# FPGA_PWR.net
KiCad netlist of a schematic drawn in Altium Designer
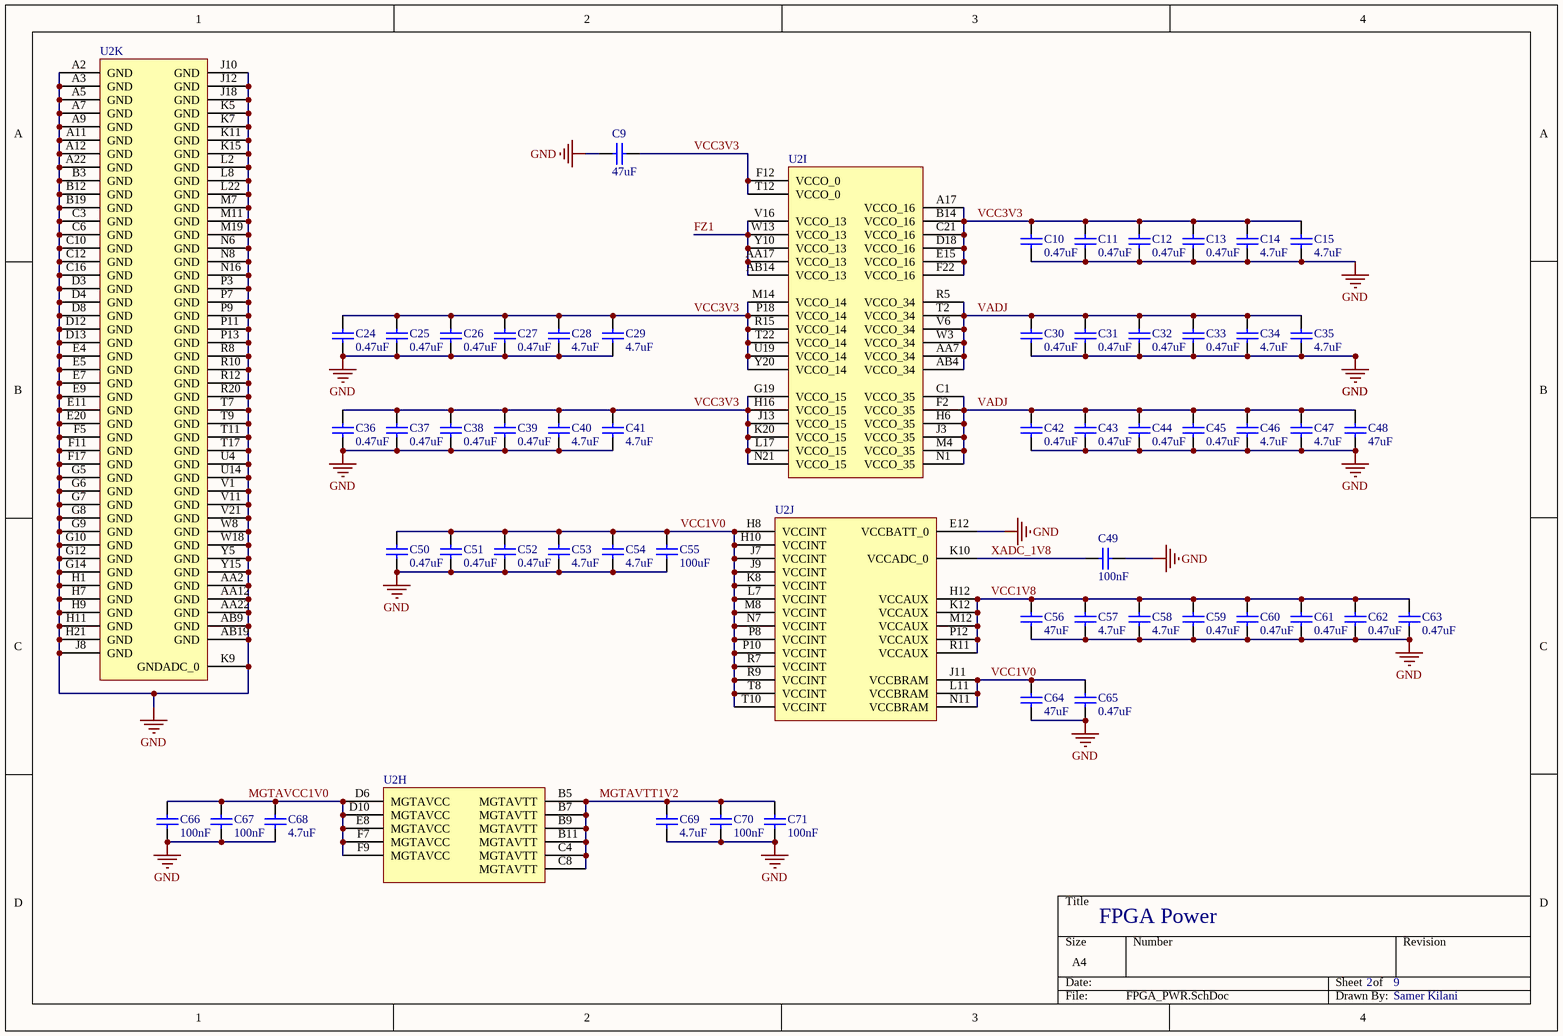
[diagram p0: FPGA_PWR.SchDoc]

(export (version "E")
  (design (tool "Eeschema 10.0.6"))
  (components
    (comp (ref "C9")
      (value "47uF")
      (footprint "C1210")
      (description "Capacitor")
      (fields (field (name "Comment") "Cap") (field (name "PUBLISHER") "Altium Limited"))
      (libsource (lib "atfclib") (part "Cap"))
    )
    (comp (ref "C10")
      (value "0.47uF")
      (footprint "C0402")
      (description "Capacitor")
      (fields (field (name "Comment") "Cap") (field (name "PUBLISHER") "Altium Limited"))
      (libsource (lib "atfclib") (part "Cap"))
    )
    (comp (ref "C11")
      (value "0.47uF")
      (footprint "C0402")
      (description "Capacitor")
      (fields (field (name "Comment") "Cap") (field (name "PUBLISHER") "Altium Limited"))
      (libsource (lib "atfclib") (part "Cap"))
    )
    (comp (ref "C12")
      (value "0.47uF")
      (footprint "C0402")
      (description "Capacitor")
      (fields (field (name "Comment") "Cap") (field (name "PUBLISHER") "Altium Limited"))
      (libsource (lib "atfclib") (part "Cap"))
    )
    (comp (ref "C13")
      (value "0.47uF")
      (footprint "C0402")
      (description "Capacitor")
      (fields (field (name "Comment") "Cap") (field (name "PUBLISHER") "Altium Limited"))
      (libsource (lib "atfclib") (part "Cap"))
    )
    (comp (ref "C14")
      (value "4.7uF")
      (footprint "C0805")
      (description "Capacitor")
      (fields (field (name "Comment") "Cap") (field (name "PUBLISHER") "Altium Limited"))
      (libsource (lib "atfclib") (part "Cap"))
    )
    (comp (ref "C15")
      (value "4.7uF")
      (footprint "C0805")
      (description "Capacitor")
      (fields (field (name "Comment") "Cap") (field (name "PUBLISHER") "Altium Limited"))
      (libsource (lib "atfclib") (part "Cap"))
    )
    (comp (ref "C24")
      (value "0.47uF")
      (footprint "C0402")
      (description "Capacitor")
      (fields (field (name "Comment") "Cap") (field (name "PUBLISHER") "Altium Limited"))
      (libsource (lib "atfclib") (part "Cap"))
    )
    (comp (ref "C25")
      (value "0.47uF")
      (footprint "C0402")
      (description "Capacitor")
      (fields (field (name "Comment") "Cap") (field (name "PUBLISHER") "Altium Limited"))
      (libsource (lib "atfclib") (part "Cap"))
    )
    (comp (ref "C26")
      (value "0.47uF")
      (footprint "C0402")
      (description "Capacitor")
      (fields (field (name "Comment") "Cap") (field (name "PUBLISHER") "Altium Limited"))
      (libsource (lib "atfclib") (part "Cap"))
    )
    (comp (ref "C27")
      (value "0.47uF")
      (footprint "C0402")
      (description "Capacitor")
      (fields (field (name "Comment") "Cap") (field (name "PUBLISHER") "Altium Limited"))
      (libsource (lib "atfclib") (part "Cap"))
    )
    (comp (ref "C28")
      (value "4.7uF")
      (footprint "C0805")
      (description "Capacitor")
      (fields (field (name "Comment") "Cap") (field (name "PUBLISHER") "Altium Limited"))
      (libsource (lib "atfclib") (part "Cap"))
    )
    (comp (ref "C29")
      (value "4.7uF")
      (footprint "C0805")
      (description "Capacitor")
      (fields (field (name "Comment") "Cap") (field (name "PUBLISHER") "Altium Limited"))
      (libsource (lib "atfclib") (part "Cap"))
    )
    (comp (ref "C30")
      (value "0.47uF")
      (footprint "C0402")
      (description "Capacitor")
      (fields (field (name "Comment") "Cap") (field (name "PUBLISHER") "Altium Limited"))
      (libsource (lib "atfclib") (part "Cap"))
    )
    (comp (ref "C31")
      (value "0.47uF")
      (footprint "C0402")
      (description "Capacitor")
      (fields (field (name "Comment") "Cap") (field (name "PUBLISHER") "Altium Limited"))
      (libsource (lib "atfclib") (part "Cap"))
    )
    (comp (ref "C32")
      (value "0.47uF")
      (footprint "C0402")
      (description "Capacitor")
      (fields (field (name "Comment") "Cap") (field (name "PUBLISHER") "Altium Limited"))
      (libsource (lib "atfclib") (part "Cap"))
    )
    (comp (ref "C33")
      (value "0.47uF")
      (footprint "C0402")
      (description "Capacitor")
      (fields (field (name "Comment") "Cap") (field (name "PUBLISHER") "Altium Limited"))
      (libsource (lib "atfclib") (part "Cap"))
    )
    (comp (ref "C34")
      (value "4.7uF")
      (footprint "C0805")
      (description "Capacitor")
      (fields (field (name "Comment") "Cap") (field (name "PUBLISHER") "Altium Limited"))
      (libsource (lib "atfclib") (part "Cap"))
    )
    (comp (ref "C35")
      (value "4.7uF")
      (footprint "C0805")
      (description "Capacitor")
      (fields (field (name "Comment") "Cap") (field (name "PUBLISHER") "Altium Limited"))
      (libsource (lib "atfclib") (part "Cap"))
    )
    (comp (ref "C36")
      (value "0.47uF")
      (footprint "C0402")
      (description "Capacitor")
      (fields (field (name "Comment") "Cap") (field (name "PUBLISHER") "Altium Limited"))
      (libsource (lib "atfclib") (part "Cap"))
    )
    (comp (ref "C37")
      (value "0.47uF")
      (footprint "C0402")
      (description "Capacitor")
      (fields (field (name "Comment") "Cap") (field (name "PUBLISHER") "Altium Limited"))
      (libsource (lib "atfclib") (part "Cap"))
    )
    (comp (ref "C38")
      (value "0.47uF")
      (footprint "C0402")
      (description "Capacitor")
      (fields (field (name "Comment") "Cap") (field (name "PUBLISHER") "Altium Limited"))
      (libsource (lib "atfclib") (part "Cap"))
    )
    (comp (ref "C39")
      (value "0.47uF")
      (footprint "C0402")
      (description "Capacitor")
      (fields (field (name "Comment") "Cap") (field (name "PUBLISHER") "Altium Limited"))
      (libsource (lib "atfclib") (part "Cap"))
    )
    (comp (ref "C40")
      (value "4.7uF")
      (footprint "C0805")
      (description "Capacitor")
      (fields (field (name "Comment") "Cap") (field (name "PUBLISHER") "Altium Limited"))
      (libsource (lib "atfclib") (part "Cap"))
    )
    (comp (ref "C41")
      (value "4.7uF")
      (footprint "C0805")
      (description "Capacitor")
      (fields (field (name "Comment") "Cap") (field (name "PUBLISHER") "Altium Limited"))
      (libsource (lib "atfclib") (part "Cap"))
    )
    (comp (ref "C42")
      (value "0.47uF")
      (footprint "C0402")
      (description "Capacitor")
      (fields (field (name "Comment") "Cap") (field (name "PUBLISHER") "Altium Limited"))
      (libsource (lib "atfclib") (part "Cap"))
    )
    (comp (ref "C43")
      (value "0.47uF")
      (footprint "C0402")
      (description "Capacitor")
      (fields (field (name "Comment") "Cap") (field (name "PUBLISHER") "Altium Limited"))
      (libsource (lib "atfclib") (part "Cap"))
    )
    (comp (ref "C44")
      (value "0.47uF")
      (footprint "C0402")
      (description "Capacitor")
      (fields (field (name "Comment") "Cap") (field (name "PUBLISHER") "Altium Limited"))
      (libsource (lib "atfclib") (part "Cap"))
    )
    (comp (ref "C45")
      (value "0.47uF")
      (footprint "C0402")
      (description "Capacitor")
      (fields (field (name "Comment") "Cap") (field (name "PUBLISHER") "Altium Limited"))
      (libsource (lib "atfclib") (part "Cap"))
    )
    (comp (ref "C46")
      (value "4.7uF")
      (footprint "C0805")
      (description "Capacitor")
      (fields (field (name "Comment") "Cap") (field (name "PUBLISHER") "Altium Limited"))
      (libsource (lib "atfclib") (part "Cap"))
    )
    (comp (ref "C47")
      (value "4.7uF")
      (footprint "C0805")
      (description "Capacitor")
      (fields (field (name "Comment") "Cap") (field (name "PUBLISHER") "Altium Limited"))
      (libsource (lib "atfclib") (part "Cap"))
    )
    (comp (ref "C48")
      (value "47uF")
      (footprint "C1210")
      (description "Capacitor")
      (fields (field (name "Comment") "Cap") (field (name "PUBLISHER") "Altium Limited"))
      (libsource (lib "atfclib") (part "Cap"))
    )
    (comp (ref "C49")
      (value "100nF")
      (footprint "C0402")
      (description "Capacitor")
      (fields (field (name "Comment") "Cap") (field (name "PUBLISHER") "Altium Limited"))
      (libsource (lib "atfclib") (part "Cap"))
    )
    (comp (ref "C50")
      (value "0.47uF")
      (footprint "C0402")
      (description "Capacitor")
      (fields (field (name "Comment") "Cap") (field (name "PUBLISHER") "Altium Limited"))
      (libsource (lib "atfclib") (part "Cap"))
    )
    (comp (ref "C51")
      (value "0.47uF")
      (footprint "C0402")
      (description "Capacitor")
      (fields (field (name "Comment") "Cap") (field (name "PUBLISHER") "Altium Limited"))
      (libsource (lib "atfclib") (part "Cap"))
    )
    (comp (ref "C52")
      (value "0.47uF")
      (footprint "C0402")
      (description "Capacitor")
      (fields (field (name "Comment") "Cap") (field (name "PUBLISHER") "Altium Limited"))
      (libsource (lib "atfclib") (part "Cap"))
    )
    (comp (ref "C53")
      (value "4.7uF")
      (footprint "C0805")
      (description "Capacitor")
      (fields (field (name "Comment") "Cap") (field (name "PUBLISHER") "Altium Limited"))
      (libsource (lib "atfclib") (part "Cap"))
    )
    (comp (ref "C54")
      (value "4.7uF")
      (footprint "C0805")
      (description "Capacitor")
      (fields (field (name "Comment") "Cap") (field (name "PUBLISHER") "Altium Limited"))
      (libsource (lib "atfclib") (part "Cap"))
    )
    (comp (ref "C55")
      (value "100uF")
      (footprint "C1210")
      (description "Capacitor")
      (fields (field (name "Comment") "Cap") (field (name "PUBLISHER") "Altium Limited"))
      (libsource (lib "atfclib") (part "Cap"))
    )
    (comp (ref "C56")
      (value "47uF")
      (footprint "C1210")
      (description "Capacitor")
      (fields (field (name "Comment") "Cap") (field (name "PUBLISHER") "Altium Limited"))
      (libsource (lib "atfclib") (part "Cap"))
    )
    (comp (ref "C57")
      (value "4.7uF")
      (footprint "C0805")
      (description "Capacitor")
      (fields (field (name "Comment") "Cap") (field (name "PUBLISHER") "Altium Limited"))
      (libsource (lib "atfclib") (part "Cap"))
    )
    (comp (ref "C58")
      (value "4.7uF")
      (footprint "C0805")
      (description "Capacitor")
      (fields (field (name "Comment") "Cap") (field (name "PUBLISHER") "Altium Limited"))
      (libsource (lib "atfclib") (part "Cap"))
    )
    (comp (ref "C59")
      (value "0.47uF")
      (footprint "C0402")
      (description "Capacitor")
      (fields (field (name "Comment") "Cap") (field (name "PUBLISHER") "Altium Limited"))
      (libsource (lib "atfclib") (part "Cap"))
    )
    (comp (ref "C60")
      (value "0.47uF")
      (footprint "C0402")
      (description "Capacitor")
      (fields (field (name "Comment") "Cap") (field (name "PUBLISHER") "Altium Limited"))
      (libsource (lib "atfclib") (part "Cap"))
    )
    (comp (ref "C61")
      (value "0.47uF")
      (footprint "C0402")
      (description "Capacitor")
      (fields (field (name "Comment") "Cap") (field (name "PUBLISHER") "Altium Limited"))
      (libsource (lib "atfclib") (part "Cap"))
    )
    (comp (ref "C62")
      (value "0.47uF")
      (footprint "C0402")
      (description "Capacitor")
      (fields (field (name "Comment") "Cap") (field (name "PUBLISHER") "Altium Limited"))
      (libsource (lib "atfclib") (part "Cap"))
    )
    (comp (ref "C63")
      (value "0.47uF")
      (footprint "C0402")
      (description "Capacitor")
      (fields (field (name "Comment") "Cap") (field (name "PUBLISHER") "Altium Limited"))
      (libsource (lib "atfclib") (part "Cap"))
    )
    (comp (ref "C64")
      (value "47uF")
      (footprint "C1210")
      (description "Capacitor")
      (fields (field (name "Comment") "Cap") (field (name "PUBLISHER") "Altium Limited"))
      (libsource (lib "atfclib") (part "Cap"))
    )
    (comp (ref "C65")
      (value "0.47uF")
      (footprint "C0402")
      (description "Capacitor")
      (fields (field (name "Comment") "Cap") (field (name "PUBLISHER") "Altium Limited"))
      (libsource (lib "atfclib") (part "Cap"))
    )
    (comp (ref "C66")
      (value "100nF")
      (footprint "C0402")
      (description "Capacitor")
      (fields (field (name "Comment") "Cap") (field (name "PUBLISHER") "Altium Limited"))
      (libsource (lib "atfclib") (part "Cap"))
    )
    (comp (ref "C67")
      (value "100nF")
      (footprint "C0402")
      (description "Capacitor")
      (fields (field (name "Comment") "Cap") (field (name "PUBLISHER") "Altium Limited"))
      (libsource (lib "atfclib") (part "Cap"))
    )
    (comp (ref "C68")
      (value "4.7uF")
      (footprint "C0805")
      (description "Capacitor")
      (fields (field (name "Comment") "Cap") (field (name "PUBLISHER") "Altium Limited"))
      (libsource (lib "atfclib") (part "Cap"))
    )
    (comp (ref "C69")
      (value "4.7uF")
      (footprint "C0805")
      (description "Capacitor")
      (fields (field (name "Comment") "Cap") (field (name "PUBLISHER") "Altium Limited"))
      (libsource (lib "atfclib") (part "Cap"))
    )
    (comp (ref "C70")
      (value "100nF")
      (footprint "C0402")
      (description "Capacitor")
      (fields (field (name "Comment") "Cap") (field (name "PUBLISHER") "Altium Limited"))
      (libsource (lib "atfclib") (part "Cap"))
    )
    (comp (ref "C71")
      (value "100nF")
      (footprint "C0402")
      (description "Capacitor")
      (fields (field (name "Comment") "Cap") (field (name "PUBLISHER") "Altium Limited"))
      (libsource (lib "atfclib") (part "Cap"))
    )
    (comp (ref "U2")
      (value "~")
      (footprint "FGG484")
      (description "Artix-7 FPGA, 250 User I/Os, 4 GTP, 484-Ball BGA, Speed Grade 1, Commercial Grade, Pb-Free")
      (fields (field (name "MANUFACTURER") "Xilinx") (field (name "PARTNUMBER") "XC7A35T-1FGG484C"))
      (libsource (lib "atfclib") (part "XC7A35T-1FGG484C"))
    )
  )
  (nets
    (net (code "1") (name "/FZ1") (class "Default")
      (node (ref "U2") (pin "AA17") (pinfunction "VCCO_13_AA17") (pintype "power_in"))
      (node (ref "U2") (pin "AB14") (pinfunction "VCCO_13_AB14") (pintype "power_in"))
      (node (ref "U2") (pin "V16") (pinfunction "VCCO_13_V16") (pintype "power_in"))
      (node (ref "U2") (pin "W13") (pinfunction "VCCO_13_W13") (pintype "power_in"))
      (node (ref "U2") (pin "Y10") (pinfunction "VCCO_13_Y10") (pintype "power_in"))
    )
    (net (code "2") (name "/MGTAVCC1V0") (class "Default")
      (node (ref "C66") (pin "1") (pinfunction "1_1") (pintype "passive"))
      (node (ref "C67") (pin "1") (pinfunction "1_1") (pintype "passive"))
      (node (ref "C68") (pin "1") (pinfunction "1_1") (pintype "passive"))
      (node (ref "U2") (pin "D10") (pinfunction "MGTAVCC_D10") (pintype "power_in"))
      (node (ref "U2") (pin "D6") (pinfunction "MGTAVCC_D6") (pintype "power_in"))
      (node (ref "U2") (pin "E8") (pinfunction "MGTAVCC_E8") (pintype "power_in"))
      (node (ref "U2") (pin "F7") (pinfunction "MGTAVCC_F7") (pintype "power_in"))
      (node (ref "U2") (pin "F9") (pinfunction "MGTAVCC_F9") (pintype "power_in"))
    )
    (net (code "3") (name "/MGTAVTT1V2") (class "Default")
      (node (ref "C69") (pin "2") (pinfunction "2_2") (pintype "passive"))
      (node (ref "C70") (pin "2") (pinfunction "2_2") (pintype "passive"))
      (node (ref "C71") (pin "2") (pinfunction "2_2") (pintype "passive"))
      (node (ref "U2") (pin "B11") (pinfunction "MGTAVTT_B11") (pintype "power_in"))
      (node (ref "U2") (pin "B5") (pinfunction "MGTAVTT_B5") (pintype "power_in"))
      (node (ref "U2") (pin "B7") (pinfunction "MGTAVTT_B7") (pintype "power_in"))
      (node (ref "U2") (pin "B9") (pinfunction "MGTAVTT_B9") (pintype "power_in"))
      (node (ref "U2") (pin "C4") (pinfunction "MGTAVTT_C4") (pintype "power_in"))
      (node (ref "U2") (pin "C8") (pinfunction "MGTAVTT_C8") (pintype "power_in"))
    )
    (net (code "4") (name "/VADJ") (class "Default")
      (node (ref "C30") (pin "1") (pinfunction "1_1") (pintype "passive"))
      (node (ref "C31") (pin "1") (pinfunction "1_1") (pintype "passive"))
      (node (ref "C32") (pin "1") (pinfunction "1_1") (pintype "passive"))
      (node (ref "C33") (pin "1") (pinfunction "1_1") (pintype "passive"))
      (node (ref "C34") (pin "1") (pinfunction "1_1") (pintype "passive"))
      (node (ref "C35") (pin "1") (pinfunction "1_1") (pintype "passive"))
      (node (ref "C42") (pin "1") (pinfunction "1_1") (pintype "passive"))
      (node (ref "C43") (pin "1") (pinfunction "1_1") (pintype "passive"))
      (node (ref "C44") (pin "1") (pinfunction "1_1") (pintype "passive"))
      (node (ref "C45") (pin "1") (pinfunction "1_1") (pintype "passive"))
      (node (ref "C46") (pin "1") (pinfunction "1_1") (pintype "passive"))
      (node (ref "C47") (pin "1") (pinfunction "1_1") (pintype "passive"))
      (node (ref "C48") (pin "1") (pinfunction "1_1") (pintype "passive"))
      (node (ref "U2") (pin "AA7") (pinfunction "VCCO_34_AA7") (pintype "power_in"))
      (node (ref "U2") (pin "AB4") (pinfunction "VCCO_34_AB4") (pintype "power_in"))
      (node (ref "U2") (pin "C1") (pinfunction "VCCO_35_C1") (pintype "power_in"))
      (node (ref "U2") (pin "F2") (pinfunction "VCCO_35_F2") (pintype "power_in"))
      (node (ref "U2") (pin "H6") (pinfunction "VCCO_35_H6") (pintype "power_in"))
      (node (ref "U2") (pin "J3") (pinfunction "VCCO_35_J3") (pintype "power_in"))
      (node (ref "U2") (pin "M4") (pinfunction "VCCO_35_M4") (pintype "power_in"))
      (node (ref "U2") (pin "N1") (pinfunction "VCCO_35_N1") (pintype "power_in"))
      (node (ref "U2") (pin "R5") (pinfunction "VCCO_34_R5") (pintype "power_in"))
      (node (ref "U2") (pin "T2") (pinfunction "VCCO_34_T2") (pintype "power_in"))
      (node (ref "U2") (pin "V6") (pinfunction "VCCO_34_V6") (pintype "power_in"))
      (node (ref "U2") (pin "W3") (pinfunction "VCCO_34_W3") (pintype "power_in"))
    )
    (net (code "5") (name "/VCC1V0") (class "Default")
      (node (ref "C50") (pin "1") (pinfunction "1_1") (pintype "passive"))
      (node (ref "C51") (pin "1") (pinfunction "1_1") (pintype "passive"))
      (node (ref "C52") (pin "1") (pinfunction "1_1") (pintype "passive"))
      (node (ref "C53") (pin "1") (pinfunction "1_1") (pintype "passive"))
      (node (ref "C54") (pin "1") (pinfunction "1_1") (pintype "passive"))
      (node (ref "C55") (pin "1") (pinfunction "1_1") (pintype "passive"))
      (node (ref "C64") (pin "1") (pinfunction "1_1") (pintype "passive"))
      (node (ref "C65") (pin "1") (pinfunction "1_1") (pintype "passive"))
      (node (ref "U2") (pin "H10") (pinfunction "VCCINT_H10") (pintype "power_in"))
      (node (ref "U2") (pin "H8") (pinfunction "VCCINT_H8") (pintype "power_in"))
      (node (ref "U2") (pin "J11") (pinfunction "VCCBRAM_J11") (pintype "power_in"))
      (node (ref "U2") (pin "J7") (pinfunction "VCCINT_J7") (pintype "power_in"))
      (node (ref "U2") (pin "J9") (pinfunction "VCCINT_J9") (pintype "power_in"))
      (node (ref "U2") (pin "K8") (pinfunction "VCCINT_K8") (pintype "power_in"))
      (node (ref "U2") (pin "L11") (pinfunction "VCCBRAM_L11") (pintype "power_in"))
      (node (ref "U2") (pin "L7") (pinfunction "VCCINT_L7") (pintype "power_in"))
      (node (ref "U2") (pin "M8") (pinfunction "VCCINT_M8") (pintype "power_in"))
      (node (ref "U2") (pin "N11") (pinfunction "VCCBRAM_N11") (pintype "power_in"))
      (node (ref "U2") (pin "N7") (pinfunction "VCCINT_N7") (pintype "power_in"))
      (node (ref "U2") (pin "P10") (pinfunction "VCCINT_P10") (pintype "power_in"))
      (node (ref "U2") (pin "P8") (pinfunction "VCCINT_P8") (pintype "power_in"))
      (node (ref "U2") (pin "R7") (pinfunction "VCCINT_R7") (pintype "power_in"))
      (node (ref "U2") (pin "R9") (pinfunction "VCCINT_R9") (pintype "power_in"))
      (node (ref "U2") (pin "T10") (pinfunction "VCCINT_T10") (pintype "power_in"))
      (node (ref "U2") (pin "T8") (pinfunction "VCCINT_T8") (pintype "power_in"))
    )
    (net (code "6") (name "/VCC1V8") (class "Default")
      (node (ref "C56") (pin "1") (pinfunction "1_1") (pintype "passive"))
      (node (ref "C57") (pin "1") (pinfunction "1_1") (pintype "passive"))
      (node (ref "C58") (pin "1") (pinfunction "1_1") (pintype "passive"))
      (node (ref "C59") (pin "1") (pinfunction "1_1") (pintype "passive"))
      (node (ref "C60") (pin "1") (pinfunction "1_1") (pintype "passive"))
      (node (ref "C61") (pin "1") (pinfunction "1_1") (pintype "passive"))
      (node (ref "C62") (pin "1") (pinfunction "1_1") (pintype "passive"))
      (node (ref "C63") (pin "1") (pinfunction "1_1") (pintype "passive"))
      (node (ref "U2") (pin "H12") (pinfunction "VCCAUX_H12") (pintype "power_in"))
      (node (ref "U2") (pin "K12") (pinfunction "VCCAUX_K12") (pintype "power_in"))
      (node (ref "U2") (pin "M12") (pinfunction "VCCAUX_M12") (pintype "power_in"))
      (node (ref "U2") (pin "P12") (pinfunction "VCCAUX_P12") (pintype "power_in"))
      (node (ref "U2") (pin "R11") (pinfunction "VCCAUX_R11") (pintype "power_in"))
    )
    (net (code "7") (name "/VCC3V3") (class "Default")
      (node (ref "C10") (pin "1") (pinfunction "1_1") (pintype "passive"))
      (node (ref "C11") (pin "1") (pinfunction "1_1") (pintype "passive"))
      (node (ref "C12") (pin "1") (pinfunction "1_1") (pintype "passive"))
      (node (ref "C13") (pin "1") (pinfunction "1_1") (pintype "passive"))
      (node (ref "C14") (pin "1") (pinfunction "1_1") (pintype "passive"))
      (node (ref "C15") (pin "1") (pinfunction "1_1") (pintype "passive"))
      (node (ref "C24") (pin "1") (pinfunction "1_1") (pintype "passive"))
      (node (ref "C25") (pin "1") (pinfunction "1_1") (pintype "passive"))
      (node (ref "C26") (pin "1") (pinfunction "1_1") (pintype "passive"))
      (node (ref "C27") (pin "1") (pinfunction "1_1") (pintype "passive"))
      (node (ref "C28") (pin "1") (pinfunction "1_1") (pintype "passive"))
      (node (ref "C29") (pin "1") (pinfunction "1_1") (pintype "passive"))
      (node (ref "C36") (pin "1") (pinfunction "1_1") (pintype "passive"))
      (node (ref "C37") (pin "1") (pinfunction "1_1") (pintype "passive"))
      (node (ref "C38") (pin "1") (pinfunction "1_1") (pintype "passive"))
      (node (ref "C39") (pin "1") (pinfunction "1_1") (pintype "passive"))
      (node (ref "C40") (pin "1") (pinfunction "1_1") (pintype "passive"))
      (node (ref "C41") (pin "1") (pinfunction "1_1") (pintype "passive"))
      (node (ref "C9") (pin "1") (pinfunction "1_1") (pintype "passive"))
      (node (ref "U2") (pin "A17") (pinfunction "VCCO_16_A17") (pintype "power_in"))
      (node (ref "U2") (pin "B14") (pinfunction "VCCO_16_B14") (pintype "power_in"))
      (node (ref "U2") (pin "C21") (pinfunction "VCCO_16_C21") (pintype "power_in"))
      (node (ref "U2") (pin "D18") (pinfunction "VCCO_16_D18") (pintype "power_in"))
      (node (ref "U2") (pin "E15") (pinfunction "VCCO_16_E15") (pintype "power_in"))
      (node (ref "U2") (pin "F12") (pinfunction "VCCO_0_F12") (pintype "power_in"))
      (node (ref "U2") (pin "F22") (pinfunction "VCCO_16_F22") (pintype "power_in"))
      (node (ref "U2") (pin "G19") (pinfunction "VCCO_15_G19") (pintype "power_in"))
      (node (ref "U2") (pin "H16") (pinfunction "VCCO_15_H16") (pintype "power_in"))
      (node (ref "U2") (pin "J13") (pinfunction "VCCO_15_J13") (pintype "power_in"))
      (node (ref "U2") (pin "K20") (pinfunction "VCCO_15_K20") (pintype "power_in"))
      (node (ref "U2") (pin "L17") (pinfunction "VCCO_15_L17") (pintype "power_in"))
      (node (ref "U2") (pin "M14") (pinfunction "VCCO_14_M14") (pintype "power_in"))
      (node (ref "U2") (pin "N21") (pinfunction "VCCO_15_N21") (pintype "power_in"))
      (node (ref "U2") (pin "P18") (pinfunction "VCCO_14_P18") (pintype "power_in"))
      (node (ref "U2") (pin "R15") (pinfunction "VCCO_14_R15") (pintype "power_in"))
      (node (ref "U2") (pin "T12") (pinfunction "VCCO_0_T12") (pintype "power_in"))
      (node (ref "U2") (pin "T22") (pinfunction "VCCO_14_T22") (pintype "power_in"))
      (node (ref "U2") (pin "U19") (pinfunction "VCCO_14_U19") (pintype "power_in"))
      (node (ref "U2") (pin "Y20") (pinfunction "VCCO_14_Y20") (pintype "power_in"))
    )
    (net (code "8") (name "/XADC_1V8") (class "Default")
      (node (ref "C49") (pin "2") (pinfunction "2_2") (pintype "passive"))
      (node (ref "U2") (pin "K10") (pinfunction "VCCADC_0_K10") (pintype "power_in"))
    )
    (net (code "9") (name "GND") (class "Default")
      (node (ref "C10") (pin "2") (pinfunction "2_2") (pintype "passive"))
      (node (ref "C11") (pin "2") (pinfunction "2_2") (pintype "passive"))
      (node (ref "C12") (pin "2") (pinfunction "2_2") (pintype "passive"))
      (node (ref "C13") (pin "2") (pinfunction "2_2") (pintype "passive"))
      (node (ref "C14") (pin "2") (pinfunction "2_2") (pintype "passive"))
      (node (ref "C15") (pin "2") (pinfunction "2_2") (pintype "passive"))
      (node (ref "C24") (pin "2") (pinfunction "2_2") (pintype "passive"))
      (node (ref "C25") (pin "2") (pinfunction "2_2") (pintype "passive"))
      (node (ref "C26") (pin "2") (pinfunction "2_2") (pintype "passive"))
      (node (ref "C27") (pin "2") (pinfunction "2_2") (pintype "passive"))
      (node (ref "C28") (pin "2") (pinfunction "2_2") (pintype "passive"))
      (node (ref "C29") (pin "2") (pinfunction "2_2") (pintype "passive"))
      (node (ref "C30") (pin "2") (pinfunction "2_2") (pintype "passive"))
      (node (ref "C31") (pin "2") (pinfunction "2_2") (pintype "passive"))
      (node (ref "C32") (pin "2") (pinfunction "2_2") (pintype "passive"))
      (node (ref "C33") (pin "2") (pinfunction "2_2") (pintype "passive"))
      (node (ref "C34") (pin "2") (pinfunction "2_2") (pintype "passive"))
      (node (ref "C35") (pin "2") (pinfunction "2_2") (pintype "passive"))
      (node (ref "C36") (pin "2") (pinfunction "2_2") (pintype "passive"))
      (node (ref "C37") (pin "2") (pinfunction "2_2") (pintype "passive"))
      (node (ref "C38") (pin "2") (pinfunction "2_2") (pintype "passive"))
      (node (ref "C39") (pin "2") (pinfunction "2_2") (pintype "passive"))
      (node (ref "C40") (pin "2") (pinfunction "2_2") (pintype "passive"))
      (node (ref "C41") (pin "2") (pinfunction "2_2") (pintype "passive"))
      (node (ref "C42") (pin "2") (pinfunction "2_2") (pintype "passive"))
      (node (ref "C43") (pin "2") (pinfunction "2_2") (pintype "passive"))
      (node (ref "C44") (pin "2") (pinfunction "2_2") (pintype "passive"))
      (node (ref "C45") (pin "2") (pinfunction "2_2") (pintype "passive"))
      (node (ref "C46") (pin "2") (pinfunction "2_2") (pintype "passive"))
      (node (ref "C47") (pin "2") (pinfunction "2_2") (pintype "passive"))
      (node (ref "C48") (pin "2") (pinfunction "2_2") (pintype "passive"))
      (node (ref "C49") (pin "1") (pinfunction "1_1") (pintype "passive"))
      (node (ref "C50") (pin "2") (pinfunction "2_2") (pintype "passive"))
      (node (ref "C51") (pin "2") (pinfunction "2_2") (pintype "passive"))
      (node (ref "C52") (pin "2") (pinfunction "2_2") (pintype "passive"))
      (node (ref "C53") (pin "2") (pinfunction "2_2") (pintype "passive"))
      (node (ref "C54") (pin "2") (pinfunction "2_2") (pintype "passive"))
      (node (ref "C55") (pin "2") (pinfunction "2_2") (pintype "passive"))
      (node (ref "C56") (pin "2") (pinfunction "2_2") (pintype "passive"))
      (node (ref "C57") (pin "2") (pinfunction "2_2") (pintype "passive"))
      (node (ref "C58") (pin "2") (pinfunction "2_2") (pintype "passive"))
      (node (ref "C59") (pin "2") (pinfunction "2_2") (pintype "passive"))
      (node (ref "C60") (pin "2") (pinfunction "2_2") (pintype "passive"))
      (node (ref "C61") (pin "2") (pinfunction "2_2") (pintype "passive"))
      (node (ref "C62") (pin "2") (pinfunction "2_2") (pintype "passive"))
      (node (ref "C63") (pin "2") (pinfunction "2_2") (pintype "passive"))
      (node (ref "C64") (pin "2") (pinfunction "2_2") (pintype "passive"))
      (node (ref "C65") (pin "2") (pinfunction "2_2") (pintype "passive"))
      (node (ref "C66") (pin "2") (pinfunction "2_2") (pintype "passive"))
      (node (ref "C67") (pin "2") (pinfunction "2_2") (pintype "passive"))
      (node (ref "C68") (pin "2") (pinfunction "2_2") (pintype "passive"))
      (node (ref "C69") (pin "1") (pinfunction "1_1") (pintype "passive"))
      (node (ref "C70") (pin "1") (pinfunction "1_1") (pintype "passive"))
      (node (ref "C71") (pin "1") (pinfunction "1_1") (pintype "passive"))
      (node (ref "C9") (pin "2") (pinfunction "2_2") (pintype "passive"))
      (node (ref "U2") (pin "A11") (pinfunction "GND_A11") (pintype "power_in"))
      (node (ref "U2") (pin "A12") (pinfunction "GND_A12") (pintype "power_in"))
      (node (ref "U2") (pin "A2") (pinfunction "GND_A2") (pintype "power_in"))
      (node (ref "U2") (pin "A22") (pinfunction "GND_A22") (pintype "power_in"))
      (node (ref "U2") (pin "A3") (pinfunction "GND_A3") (pintype "power_in"))
      (node (ref "U2") (pin "A5") (pinfunction "GND_A5") (pintype "power_in"))
      (node (ref "U2") (pin "A7") (pinfunction "GND_A7") (pintype "power_in"))
      (node (ref "U2") (pin "A9") (pinfunction "GND_A9") (pintype "power_in"))
      (node (ref "U2") (pin "AA12") (pinfunction "GND_AA12") (pintype "power_in"))
      (node (ref "U2") (pin "AA2") (pinfunction "GND_AA2") (pintype "power_in"))
      (node (ref "U2") (pin "AA22") (pinfunction "GND_AA22") (pintype "power_in"))
      (node (ref "U2") (pin "AB19") (pinfunction "GND_AB19") (pintype "power_in"))
      (node (ref "U2") (pin "AB9") (pinfunction "GND_AB9") (pintype "power_in"))
      (node (ref "U2") (pin "B12") (pinfunction "GND_B12") (pintype "power_in"))
      (node (ref "U2") (pin "B19") (pinfunction "GND_B19") (pintype "power_in"))
      (node (ref "U2") (pin "B3") (pinfunction "GND_B3") (pintype "power_in"))
      (node (ref "U2") (pin "C10") (pinfunction "GND_C10") (pintype "power_in"))
      (node (ref "U2") (pin "C12") (pinfunction "GND_C12") (pintype "power_in"))
      (node (ref "U2") (pin "C16") (pinfunction "GND_C16") (pintype "power_in"))
      (node (ref "U2") (pin "C3") (pinfunction "GND_C3") (pintype "power_in"))
      (node (ref "U2") (pin "C6") (pinfunction "GND_C6") (pintype "power_in"))
      (node (ref "U2") (pin "D12") (pinfunction "GND_D12") (pintype "power_in"))
      (node (ref "U2") (pin "D13") (pinfunction "GND_D13") (pintype "power_in"))
      (node (ref "U2") (pin "D3") (pinfunction "GND_D3") (pintype "power_in"))
      (node (ref "U2") (pin "D4") (pinfunction "GND_D4") (pintype "power_in"))
      (node (ref "U2") (pin "D8") (pinfunction "GND_D8") (pintype "power_in"))
      (node (ref "U2") (pin "E11") (pinfunction "GND_E11") (pintype "power_in"))
      (node (ref "U2") (pin "E12") (pinfunction "VCCBATT_0_E12") (pintype "power_in"))
      (node (ref "U2") (pin "E20") (pinfunction "GND_E20") (pintype "power_in"))
      (node (ref "U2") (pin "E4") (pinfunction "GND_E4") (pintype "power_in"))
      (node (ref "U2") (pin "E5") (pinfunction "GND_E5") (pintype "power_in"))
      (node (ref "U2") (pin "E7") (pinfunction "GND_E7") (pintype "power_in"))
      (node (ref "U2") (pin "E9") (pinfunction "GND_E9") (pintype "power_in"))
      (node (ref "U2") (pin "F11") (pinfunction "GND_F11") (pintype "power_in"))
      (node (ref "U2") (pin "F17") (pinfunction "GND_F17") (pintype "power_in"))
      (node (ref "U2") (pin "F5") (pinfunction "GND_F5") (pintype "power_in"))
      (node (ref "U2") (pin "G10") (pinfunction "GND_G10") (pintype "power_in"))
      (node (ref "U2") (pin "G12") (pinfunction "GND_G12") (pintype "power_in"))
      (node (ref "U2") (pin "G14") (pinfunction "GND_G14") (pintype "power_in"))
      (node (ref "U2") (pin "G5") (pinfunction "GND_G5") (pintype "power_in"))
      (node (ref "U2") (pin "G6") (pinfunction "GND_G6") (pintype "power_in"))
      (node (ref "U2") (pin "G7") (pinfunction "GND_G7") (pintype "power_in"))
      (node (ref "U2") (pin "G8") (pinfunction "GND_G8") (pintype "power_in"))
      (node (ref "U2") (pin "G9") (pinfunction "GND_G9") (pintype "power_in"))
      (node (ref "U2") (pin "H1") (pinfunction "GND_H1") (pintype "power_in"))
      (node (ref "U2") (pin "H11") (pinfunction "GND_H11") (pintype "power_in"))
      (node (ref "U2") (pin "H21") (pinfunction "GND_H21") (pintype "power_in"))
      (node (ref "U2") (pin "H7") (pinfunction "GND_H7") (pintype "power_in"))
      (node (ref "U2") (pin "H9") (pinfunction "GND_H9") (pintype "power_in"))
      (node (ref "U2") (pin "J10") (pinfunction "GND_J10") (pintype "power_in"))
      (node (ref "U2") (pin "J12") (pinfunction "GND_J12") (pintype "power_in"))
      (node (ref "U2") (pin "J18") (pinfunction "GND_J18") (pintype "power_in"))
      (node (ref "U2") (pin "J8") (pinfunction "GND_J8") (pintype "power_in"))
      (node (ref "U2") (pin "K11") (pinfunction "GND_K11") (pintype "power_in"))
      (node (ref "U2") (pin "K15") (pinfunction "GND_K15") (pintype "power_in"))
      (node (ref "U2") (pin "K5") (pinfunction "GND_K5") (pintype "power_in"))
      (node (ref "U2") (pin "K7") (pinfunction "GND_K7") (pintype "power_in"))
      (node (ref "U2") (pin "K9") (pinfunction "GNDADC_0_K9") (pintype "power_in"))
      (node (ref "U2") (pin "L2") (pinfunction "GND_L2") (pintype "power_in"))
      (node (ref "U2") (pin "L22") (pinfunction "GND_L22") (pintype "power_in"))
      (node (ref "U2") (pin "L8") (pinfunction "GND_L8") (pintype "power_in"))
      (node (ref "U2") (pin "M11") (pinfunction "GND_M11") (pintype "power_in"))
      (node (ref "U2") (pin "M19") (pinfunction "GND_M19") (pintype "power_in"))
      (node (ref "U2") (pin "M7") (pinfunction "GND_M7") (pintype "power_in"))
      (node (ref "U2") (pin "N16") (pinfunction "GND_N16") (pintype "power_in"))
      (node (ref "U2") (pin "N6") (pinfunction "GND_N6") (pintype "power_in"))
      (node (ref "U2") (pin "N8") (pinfunction "GND_N8") (pintype "power_in"))
      (node (ref "U2") (pin "P11") (pinfunction "GND_P11") (pintype "power_in"))
      (node (ref "U2") (pin "P13") (pinfunction "GND_P13") (pintype "power_in"))
      (node (ref "U2") (pin "P3") (pinfunction "GND_P3") (pintype "power_in"))
      (node (ref "U2") (pin "P7") (pinfunction "GND_P7") (pintype "power_in"))
      (node (ref "U2") (pin "P9") (pinfunction "GND_P9") (pintype "power_in"))
      (node (ref "U2") (pin "R10") (pinfunction "GND_R10") (pintype "power_in"))
      (node (ref "U2") (pin "R12") (pinfunction "GND_R12") (pintype "power_in"))
      (node (ref "U2") (pin "R20") (pinfunction "GND_R20") (pintype "power_in"))
      (node (ref "U2") (pin "R8") (pinfunction "GND_R8") (pintype "power_in"))
      (node (ref "U2") (pin "T11") (pinfunction "GND_T11") (pintype "power_in"))
      (node (ref "U2") (pin "T17") (pinfunction "GND_T17") (pintype "power_in"))
      (node (ref "U2") (pin "T7") (pinfunction "GND_T7") (pintype "power_in"))
      (node (ref "U2") (pin "T9") (pinfunction "GND_T9") (pintype "power_in"))
      (node (ref "U2") (pin "U14") (pinfunction "GND_U14") (pintype "power_in"))
      (node (ref "U2") (pin "U4") (pinfunction "GND_U4") (pintype "power_in"))
      (node (ref "U2") (pin "V1") (pinfunction "GND_V1") (pintype "power_in"))
      (node (ref "U2") (pin "V11") (pinfunction "GND_V11") (pintype "power_in"))
      (node (ref "U2") (pin "V21") (pinfunction "GND_V21") (pintype "power_in"))
      (node (ref "U2") (pin "W18") (pinfunction "GND_W18") (pintype "power_in"))
      (node (ref "U2") (pin "W8") (pinfunction "GND_W8") (pintype "power_in"))
      (node (ref "U2") (pin "Y15") (pinfunction "GND_Y15") (pintype "power_in"))
      (node (ref "U2") (pin "Y5") (pinfunction "GND_Y5") (pintype "power_in"))
    )
  )
)
